# 04_-_Display_Pi_Zero_USB_Host.net
KiCad netlist of a schematic drawn in Altium Designer
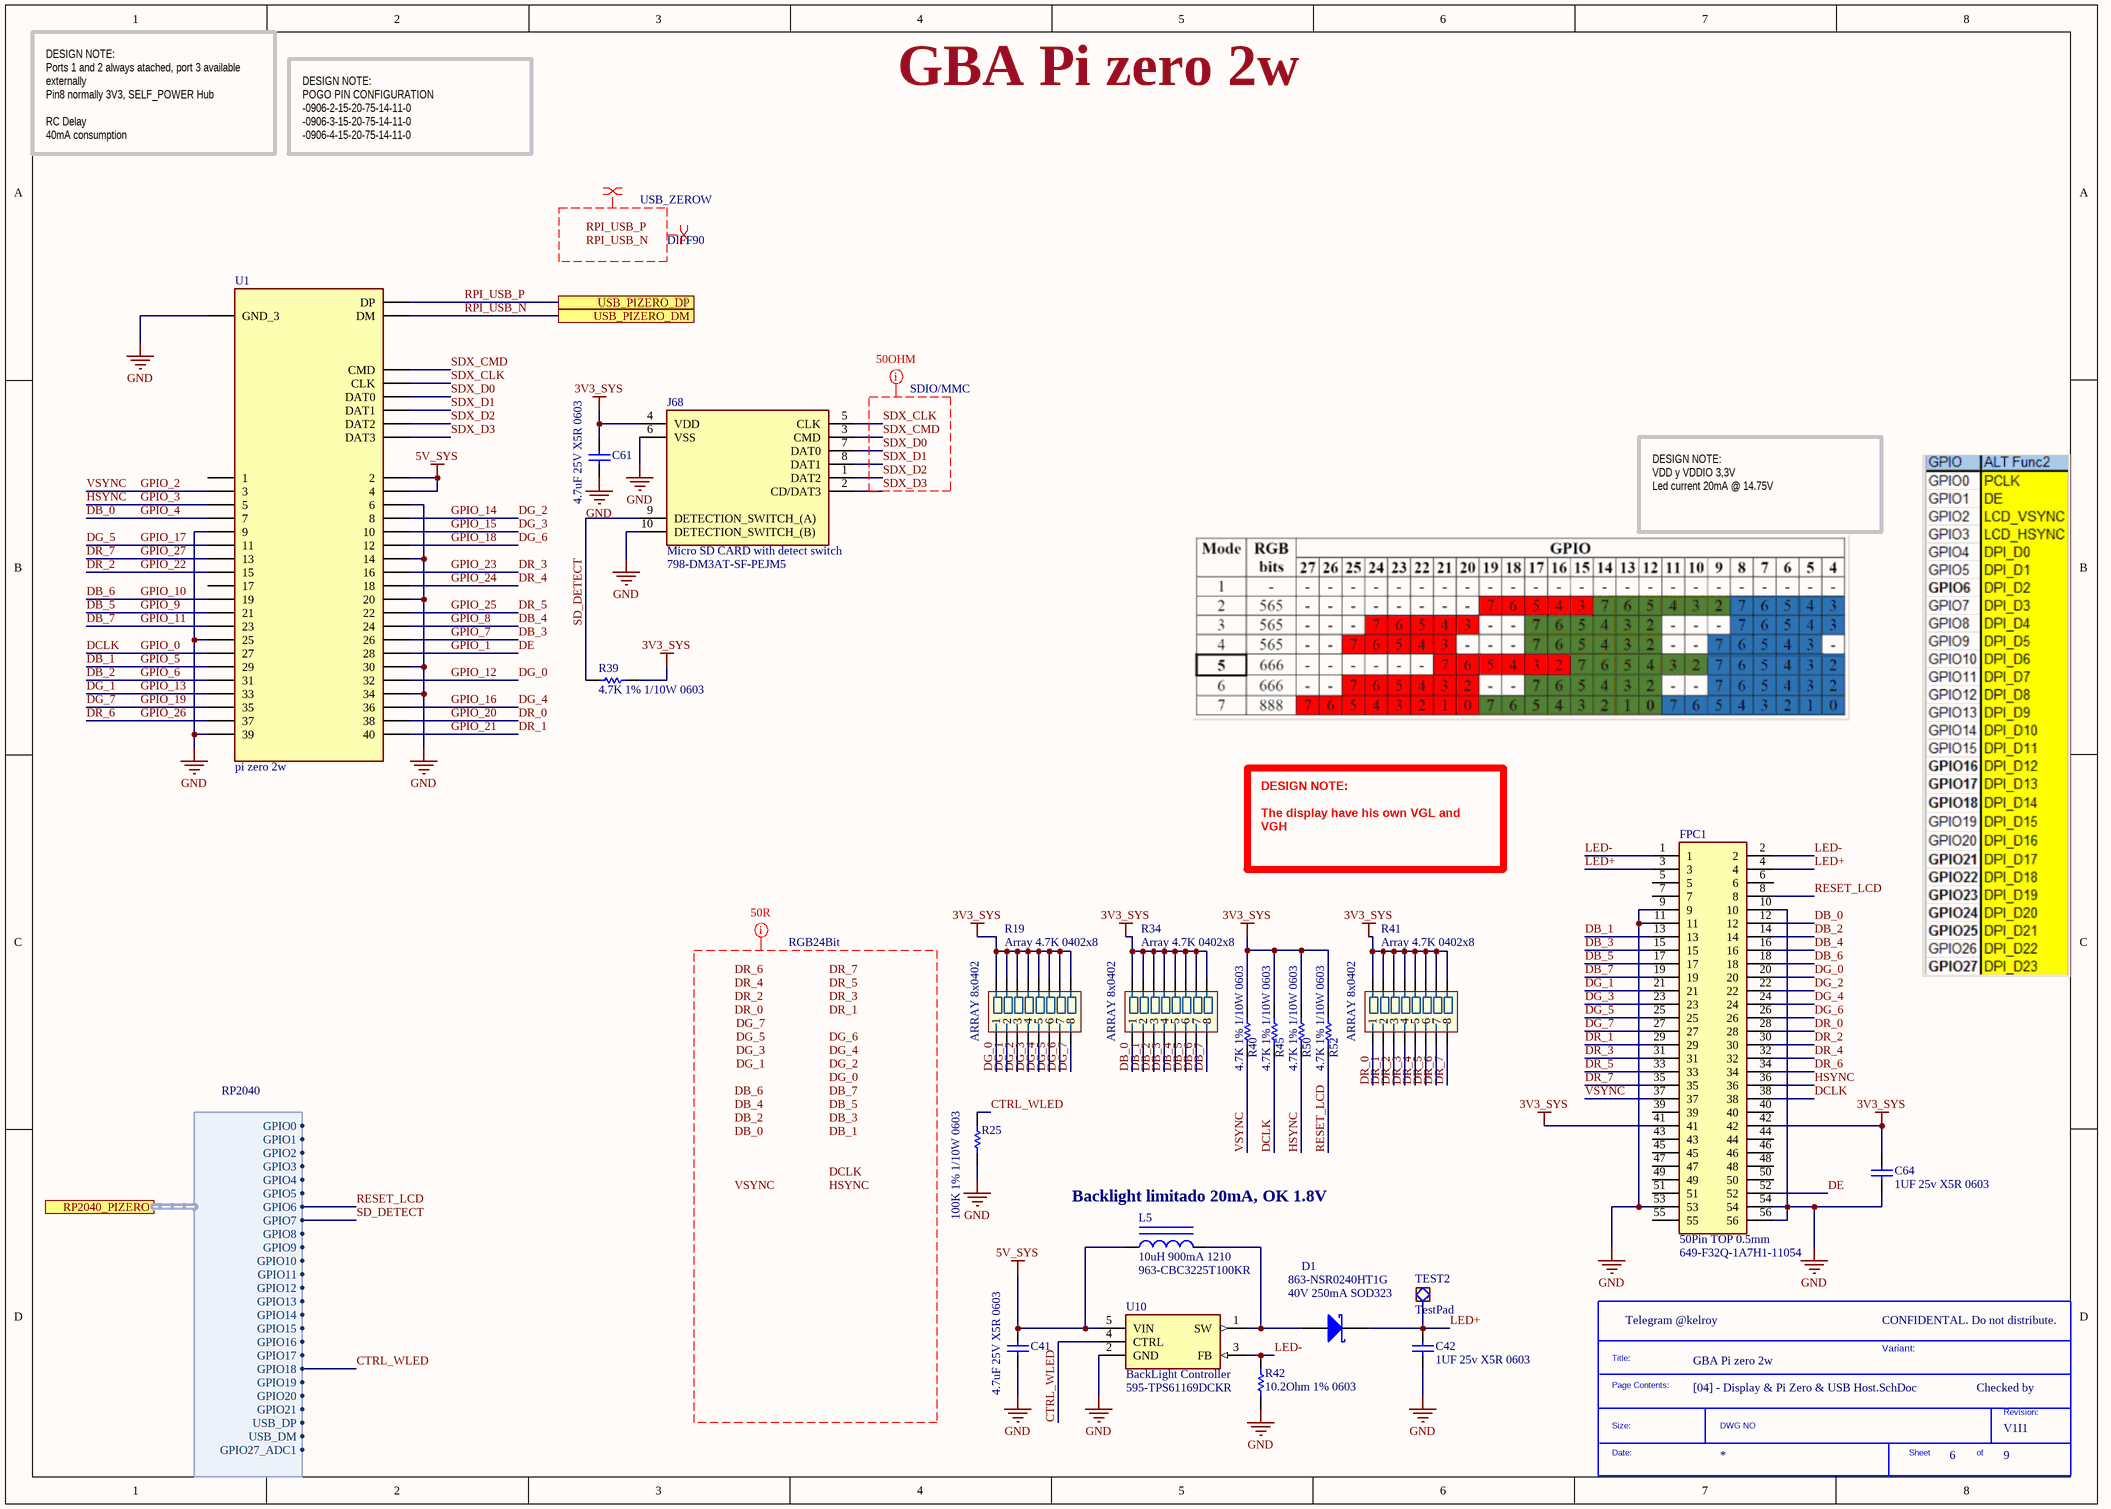
[diagram p0: [04] - Display & Pi Zero & USB Host.SchDoc]

(export (version "E")
  (design (tool "Eeschema 10.0.6"))
  (components
    (comp (ref "C41")
      (value "4.7uF 25V X5R 0603")
      (footprint "C 0603/1608")
      (description "Condensadores de cerámica multicapa (MLCC- SMD/SMT) 0603 25VDC 4.7uF 20% X5R")
      (libsource (lib "Kelboy") (part "TMK107BBJ475MA-T"))
    )
    (comp (ref "C42")
      (value "1UF 25v X5R 0603")
      (footprint "C 0603/1608")
      (description "CAP CER 1UF 25V X5R 0603")
      (fields
        (field (name "MANUFACTURER") "Yageo")
        (field (name "MANUFACTURER PART NUMBER") "CC0603KRX5R8BB105")
      )
      (libsource (lib "CM3Board_V1I2") (part "CC0603KRX5R8BB105"))
    )
    (comp (ref "C61")
      (value "4.7uF 25V X5R 0603")
      (footprint "C 0603/1608")
      (description "Condensadores de cerámica multicapa (MLCC- SMD/SMT) 0603 25VDC 4.7uF 20% X5R")
      (libsource (lib "Kelboy") (part "TMK107BBJ475MA-T"))
    )
    (comp (ref "C64")
      (value "1UF 25v X5R 0603")
      (footprint "C 0603/1608")
      (description "CAP CER 1UF 25V X5R 0603")
      (fields
        (field (name "MANUFACTURER") "Yageo")
        (field (name "MANUFACTURER PART NUMBER") "CC0603KRX5R8BB105")
      )
      (libsource (lib "CM3Board_V1I2") (part "CC0603KRX5R8BB105"))
    )
    (comp (ref "D1")
      (value "40V 250mA SOD323")
      (footprint "SOD-323")
      (description "DIODE SCHOTTKY 40V 250MA SOD323")
      (fields
        (field (name "MANUFACTURER") "ON Semiconductor")
        (field (name "MANUFACTURER PART NUMBER") "NSR0240HT1G")
        (field (name "SUPPLIER PART NUMBER 1") "863-NSR0240HT1G")
      )
      (libsource (lib "DPI_LVDS") (part "NSR0240HT1G"))
    )
    (comp (ref "FPC1")
      (value "50Pin TOP 0.5mm")
      (footprint "XF2M54151AH")
      (description "FPC/FFC Connector Socket 54 Position 0.5mm Top Contact Solder Right Angle Surface Mount T/R")
      (fields
        (field (name "MANUFACTURER") "Amphenol ICC / FCI")
        (field (name "MANUFACTURER PART NUMBER") "F32Q-1A7H1-11054")
        (field (name "SUPPLIER PART NUMBER 1") "649-F32Q-1A7H1-11054")
      )
      (libsource (lib "GBA") (part "F32Q-1A7H1-11054"))
    )
    (comp (ref "J68")
      (value "Micro SD CARD with detect switch")
      (footprint "DM3AT-SF-PEJM5_1")
      (description "CONN MICRO SD CARD PUSH-PUSH R/A")
      (fields (field (name "SUPPLIER PART NUMBER 1") "798-DM3AT-SF-PEJM5"))
      (libsource (lib "Kelboy") (part "DM3AT-SF-PEJM5"))
    )
    (comp (ref "L5")
      (value "10uH 900mA 1210")
      (footprint "L 1210/3225")
      (description "Fixed Inductors 1210 10uH 172.9mOhms +/-10% 900mA HiCur")
      (fields
        (field (name "MANUFACTURER") "Taiyo Yuden")
        (field (name "MANUFACTURER PART NUMBER") "CBC3225T100KR")
        (field (name "SUPPLIER PART NUMBER 1") "963-CBC3225T100KR")
      )
      (libsource (lib "DPI_LVDS") (part "CBC3225T100KR"))
    )
    (comp (ref "R19")
      (value "Array 4.7K 0402x8")
      (footprint "YAG_YC248-M")
      (description "RES ARRAY 8 RES 4.7K OHM 1606")
      (fields (field (name "TOLERANCE") "5%"))
      (libsource (lib "CM3Board_V1I2") (part "YC248-JR-074K7L"))
    )
    (comp (ref "R25")
      (value "100K 1% 1/10W 0603")
      (footprint "R 0603/1608")
      (description "RES SMD 100K OHM 1% 1/10W 0603")
      (fields
        (field (name "MANUFACTURER") "Yageo")
        (field (name "MANUFACTURER PART NUMBER") "RC0603FR-07100KL")
      )
      (libsource (lib "altium-import") (part "root_1_RC0603FR-07100KL_"))
    )
    (comp (ref "R34")
      (value "Array 4.7K 0402x8")
      (footprint "YAG_YC248-M")
      (description "RES ARRAY 8 RES 4.7K OHM 1606")
      (fields (field (name "TOLERANCE") "5%"))
      (libsource (lib "CM3Board_V1I2") (part "YC248-JR-074K7L"))
    )
    (comp (ref "R39")
      (value "4.7K 1% 1/10W 0603")
      (footprint "R 0603/1608")
      (description "RES SMD 4.7K OHM 1% 1/10W 0603")
      (fields
        (field (name "MANUFACTURER") "Yageo")
        (field (name "MANUFACTURER PART NUMBER") "RC0603FR-074K7L")
      )
      (libsource (lib "CM3Board_V1I2") (part "RC0603FR-074K7L"))
    )
    (comp (ref "R40")
      (value "4.7K 1% 1/10W 0603")
      (footprint "R 0603/1608")
      (description "RES SMD 4.7K OHM 1% 1/10W 0603")
      (fields
        (field (name "MANUFACTURER") "Yageo")
        (field (name "MANUFACTURER PART NUMBER") "RC0603FR-074K7L")
      )
      (libsource (lib "CM3Board_V1I2") (part "RC0603FR-074K7L"))
    )
    (comp (ref "R41")
      (value "Array 4.7K 0402x8")
      (footprint "YAG_YC248-M")
      (description "RES ARRAY 8 RES 4.7K OHM 1606")
      (fields (field (name "TOLERANCE") "5%"))
      (libsource (lib "CM3Board_V1I2") (part "YC248-JR-074K7L"))
    )
    (comp (ref "R42")
      (value "10.2Ohm 1% 0603")
      (footprint "R 0603/1608")
      (description "RES SMD 10.2 OHM 1% 1/10W 0603")
      (fields (field (name "TOLERANCE") "1%"))
      (libsource (lib "Kelboy") (part "RC0603FR-0710R2L"))
    )
    (comp (ref "R45")
      (value "4.7K 1% 1/10W 0603")
      (footprint "R 0603/1608")
      (description "RES SMD 4.7K OHM 1% 1/10W 0603")
      (fields
        (field (name "MANUFACTURER") "Yageo")
        (field (name "MANUFACTURER PART NUMBER") "RC0603FR-074K7L")
      )
      (libsource (lib "CM3Board_V1I2") (part "RC0603FR-074K7L"))
    )
    (comp (ref "R50")
      (value "4.7K 1% 1/10W 0603")
      (footprint "R 0603/1608")
      (description "RES SMD 4.7K OHM 1% 1/10W 0603")
      (fields
        (field (name "MANUFACTURER") "Yageo")
        (field (name "MANUFACTURER PART NUMBER") "RC0603FR-074K7L")
      )
      (libsource (lib "CM3Board_V1I2") (part "RC0603FR-074K7L"))
    )
    (comp (ref "R52")
      (value "4.7K 1% 1/10W 0603")
      (footprint "R 0603/1608")
      (description "RES SMD 4.7K OHM 1% 1/10W 0603")
      (fields
        (field (name "MANUFACTURER") "Yageo")
        (field (name "MANUFACTURER PART NUMBER") "RC0603FR-074K7L")
      )
      (libsource (lib "CM3Board_V1I2") (part "RC0603FR-074K7L"))
    )
    (comp (ref "TEST2")
      (value "TestPad")
      (footprint "TestPad")
      (description "Probe Pad, SMT, ROUND, 2.0MM")
      (libsource (lib "CM3Board") (part "PP_SMT_ROUND_2MM"))
    )
    (comp (ref "U1")
      (value "pi zero 2w")
      (footprint "Pi 2 Zero W - Release")
      (description "Comprar los pogo 575-906015  x 60 y los de los tornillos x4 710-9774025151R")
      (libsource (lib "GBA") (part "PI ZERO 2W"))
    )
    (comp (ref "U10")
      (value "BackLight Controller")
      (footprint "SOT65P210X110-5N")
      (description "IC LED DRVR RGLTR DIM 1.8A SC70")
      (fields
        (field (name "MANUFACTURER") "Texas Instruments")
        (field (name "MANUFACTURER PART NUMBER") "TPS61169DCKR")
        (field (name "SUPPLIER PART NUMBER 1") "595-TPS61169DCKR")
      )
      (libsource (lib "DPI_LVDS") (part "TPS61169DCKR"))
    )
  )
  (nets
    (net (code "2") (name "/CTRL_WLED") (class "Default")
      (node (ref "R25") (pin "2") (pinfunction "2_2") (pintype "passive"))
      (node (ref "U10") (pin "4") (pinfunction "CTRL_4") (pintype "passive"))
    )
    (net (code "3") (name "/DB_0") (class "Default")
      (node (ref "FPC1") (pin "12") (pinfunction "12_12") (pintype "passive"))
      (node (ref "R34") (pin "1") (pinfunction "1_1") (pintype "passive"))
      (node (ref "U1") (pin "7") (pinfunction "7_7") (pintype "passive"))
    )
    (net (code "4") (name "/DB_1") (class "Default")
      (node (ref "FPC1") (pin "13") (pinfunction "13_13") (pintype "passive"))
      (node (ref "R34") (pin "2") (pinfunction "2_2") (pintype "passive"))
      (node (ref "U1") (pin "29") (pinfunction "29_29") (pintype "passive"))
    )
    (net (code "5") (name "/DB_2") (class "Default")
      (node (ref "FPC1") (pin "14") (pinfunction "14_14") (pintype "passive"))
      (node (ref "R34") (pin "3") (pinfunction "3_3") (pintype "passive"))
      (node (ref "U1") (pin "31") (pinfunction "31_31") (pintype "passive"))
    )
    (net (code "6") (name "/DB_3") (class "Default")
      (node (ref "FPC1") (pin "15") (pinfunction "15_15") (pintype "passive"))
      (node (ref "R34") (pin "4") (pinfunction "4_4") (pintype "passive"))
      (node (ref "U1") (pin "26") (pinfunction "26_26") (pintype "passive"))
    )
    (net (code "7") (name "/DB_4") (class "Default")
      (node (ref "FPC1") (pin "16") (pinfunction "16_16") (pintype "passive"))
      (node (ref "R34") (pin "5") (pinfunction "5_5") (pintype "passive"))
      (node (ref "U1") (pin "24") (pinfunction "24_24") (pintype "passive"))
    )
    (net (code "8") (name "/DB_5") (class "Default")
      (node (ref "FPC1") (pin "17") (pinfunction "17_17") (pintype "passive"))
      (node (ref "R34") (pin "6") (pinfunction "6_6") (pintype "passive"))
      (node (ref "U1") (pin "21") (pinfunction "21_21") (pintype "passive"))
    )
    (net (code "9") (name "/DB_6") (class "Default")
      (node (ref "FPC1") (pin "18") (pinfunction "18_18") (pintype "passive"))
      (node (ref "R34") (pin "7") (pinfunction "7_7") (pintype "passive"))
      (node (ref "U1") (pin "19") (pinfunction "19_19") (pintype "passive"))
    )
    (net (code "10") (name "/DB_7") (class "Default")
      (node (ref "FPC1") (pin "19") (pinfunction "19_19") (pintype "passive"))
      (node (ref "R34") (pin "8") (pinfunction "8_8") (pintype "passive"))
      (node (ref "U1") (pin "23") (pinfunction "23_23") (pintype "passive"))
    )
    (net (code "11") (name "/DCLK") (class "Default")
      (node (ref "FPC1") (pin "38") (pinfunction "38_38") (pintype "passive"))
      (node (ref "R45") (pin "1") (pinfunction "1_1") (pintype "passive"))
      (node (ref "U1") (pin "27") (pinfunction "27_27") (pintype "passive"))
    )
    (net (code "12") (name "/DE") (class "Default")
      (node (ref "FPC1") (pin "52") (pinfunction "52_52") (pintype "passive"))
      (node (ref "U1") (pin "28") (pinfunction "28_28") (pintype "passive"))
    )
    (net (code "13") (name "/DG_0") (class "Default")
      (node (ref "FPC1") (pin "20") (pinfunction "20_20") (pintype "passive"))
      (node (ref "R19") (pin "1") (pinfunction "1_1") (pintype "passive"))
      (node (ref "U1") (pin "32") (pinfunction "32_32") (pintype "passive"))
    )
    (net (code "14") (name "/DG_1") (class "Default")
      (node (ref "FPC1") (pin "21") (pinfunction "21_21") (pintype "passive"))
      (node (ref "R19") (pin "2") (pinfunction "2_2") (pintype "passive"))
      (node (ref "U1") (pin "33") (pinfunction "33_33") (pintype "passive"))
    )
    (net (code "15") (name "/DG_2") (class "Default")
      (node (ref "FPC1") (pin "22") (pinfunction "22_22") (pintype "passive"))
      (node (ref "R19") (pin "3") (pinfunction "3_3") (pintype "passive"))
      (node (ref "U1") (pin "8") (pinfunction "8_8") (pintype "passive"))
    )
    (net (code "16") (name "/DG_3") (class "Default")
      (node (ref "FPC1") (pin "23") (pinfunction "23_23") (pintype "passive"))
      (node (ref "R19") (pin "4") (pinfunction "4_4") (pintype "passive"))
      (node (ref "U1") (pin "10") (pinfunction "10_10") (pintype "passive"))
    )
    (net (code "17") (name "/DG_4") (class "Default")
      (node (ref "FPC1") (pin "24") (pinfunction "24_24") (pintype "passive"))
      (node (ref "R19") (pin "5") (pinfunction "5_5") (pintype "passive"))
      (node (ref "U1") (pin "36") (pinfunction "36_36") (pintype "passive"))
    )
    (net (code "18") (name "/DG_5") (class "Default")
      (node (ref "FPC1") (pin "25") (pinfunction "25_25") (pintype "passive"))
      (node (ref "R19") (pin "6") (pinfunction "6_6") (pintype "passive"))
      (node (ref "U1") (pin "11") (pinfunction "11_11") (pintype "passive"))
    )
    (net (code "19") (name "/DG_6") (class "Default")
      (node (ref "FPC1") (pin "26") (pinfunction "26_26") (pintype "passive"))
      (node (ref "R19") (pin "7") (pinfunction "7_7") (pintype "passive"))
      (node (ref "U1") (pin "12") (pinfunction "12_12") (pintype "passive"))
    )
    (net (code "20") (name "/DG_7") (class "Default")
      (node (ref "FPC1") (pin "27") (pinfunction "27_27") (pintype "passive"))
      (node (ref "R19") (pin "8") (pinfunction "8_8") (pintype "passive"))
      (node (ref "U1") (pin "35") (pinfunction "35_35") (pintype "passive"))
    )
    (net (code "21") (name "/DR_0") (class "Default")
      (node (ref "FPC1") (pin "28") (pinfunction "28_28") (pintype "passive"))
      (node (ref "R41") (pin "1") (pinfunction "1_1") (pintype "passive"))
      (node (ref "U1") (pin "38") (pinfunction "38_38") (pintype "passive"))
    )
    (net (code "22") (name "/DR_1") (class "Default")
      (node (ref "FPC1") (pin "29") (pinfunction "29_29") (pintype "passive"))
      (node (ref "R41") (pin "2") (pinfunction "2_2") (pintype "passive"))
      (node (ref "U1") (pin "40") (pinfunction "40_40") (pintype "passive"))
    )
    (net (code "23") (name "/DR_2") (class "Default")
      (node (ref "FPC1") (pin "30") (pinfunction "30_30") (pintype "passive"))
      (node (ref "R41") (pin "3") (pinfunction "3_3") (pintype "passive"))
      (node (ref "U1") (pin "15") (pinfunction "15_15") (pintype "passive"))
    )
    (net (code "24") (name "/DR_3") (class "Default")
      (node (ref "FPC1") (pin "31") (pinfunction "31_31") (pintype "passive"))
      (node (ref "R41") (pin "4") (pinfunction "4_4") (pintype "passive"))
      (node (ref "U1") (pin "16") (pinfunction "16_16") (pintype "passive"))
    )
    (net (code "25") (name "/DR_4") (class "Default")
      (node (ref "FPC1") (pin "32") (pinfunction "32_32") (pintype "passive"))
      (node (ref "R41") (pin "5") (pinfunction "5_5") (pintype "passive"))
      (node (ref "U1") (pin "18") (pinfunction "18_18") (pintype "passive"))
    )
    (net (code "26") (name "/DR_5") (class "Default")
      (node (ref "FPC1") (pin "33") (pinfunction "33_33") (pintype "passive"))
      (node (ref "R41") (pin "6") (pinfunction "6_6") (pintype "passive"))
      (node (ref "U1") (pin "22") (pinfunction "22_22") (pintype "passive"))
    )
    (net (code "27") (name "/DR_6") (class "Default")
      (node (ref "FPC1") (pin "34") (pinfunction "34_34") (pintype "passive"))
      (node (ref "R41") (pin "7") (pinfunction "7_7") (pintype "passive"))
      (node (ref "U1") (pin "37") (pinfunction "37_37") (pintype "passive"))
    )
    (net (code "28") (name "/DR_7") (class "Default")
      (node (ref "FPC1") (pin "35") (pinfunction "35_35") (pintype "passive"))
      (node (ref "R41") (pin "8") (pinfunction "8_8") (pintype "passive"))
      (node (ref "U1") (pin "13") (pinfunction "13_13") (pintype "passive"))
    )
    (net (code "29") (name "/GPIO_2") (class "Default")
      (node (ref "FPC1") (pin "37") (pinfunction "37_37") (pintype "passive"))
      (node (ref "R40") (pin "1") (pinfunction "1_1") (pintype "passive"))
      (node (ref "U1") (pin "3") (pinfunction "3_3") (pintype "passive"))
    )
    (net (code "30") (name "/GPIO_3") (class "Default")
      (node (ref "FPC1") (pin "36") (pinfunction "36_36") (pintype "passive"))
      (node (ref "R50") (pin "1") (pinfunction "1_1") (pintype "passive"))
      (node (ref "U1") (pin "5") (pinfunction "5_5") (pintype "passive"))
    )
    (net (code "31") (name "/LED+") (class "Default")
      (node (ref "C42") (pin "1") (pinfunction "1_1") (pintype "passive"))
      (node (ref "D1") (pin "1") (pinfunction "K_1") (pintype "passive"))
      (node (ref "FPC1") (pin "3") (pinfunction "3_3") (pintype "passive"))
      (node (ref "FPC1") (pin "4") (pinfunction "4_4") (pintype "passive"))
      (node (ref "TEST2") (pin "1") (pinfunction "1_1") (pintype "passive"))
    )
    (net (code "32") (name "/LED-") (class "Default")
      (node (ref "FPC1") (pin "1") (pinfunction "1_1") (pintype "passive"))
      (node (ref "FPC1") (pin "2") (pinfunction "2_2") (pintype "passive"))
      (node (ref "R42") (pin "2") (pinfunction "2_2") (pintype "passive"))
      (node (ref "U10") (pin "3") (pinfunction "FB_3") (pintype "input"))
    )
    (net (code "33") (name "/RESET_LCD") (class "Default")
      (node (ref "FPC1") (pin "8") (pinfunction "8_8") (pintype "passive"))
      (node (ref "R52") (pin "1") (pinfunction "1_1") (pintype "passive"))
    )
    (net (code "34") (name "/RPI_USB_N") (class "Default")
      (node (ref "U1") (pin "DM") (pinfunction "DM_DM") (pintype "passive"))
    )
    (net (code "35") (name "/RPI_USB_P") (class "Default")
      (node (ref "U1") (pin "DP") (pinfunction "DP_DP") (pintype "passive"))
    )
    (net (code "36") (name "/SDX_CLK") (class "Default")
      (node (ref "J68") (pin "5") (pinfunction "CLK_5") (pintype "passive"))
      (node (ref "U1") (pin "CLK") (pinfunction "CLK_CLK") (pintype "passive"))
    )
    (net (code "37") (name "/SDX_CMD") (class "Default")
      (node (ref "J68") (pin "3") (pinfunction "CMD_3") (pintype "passive"))
      (node (ref "U1") (pin "CMD") (pinfunction "CMD_CMD") (pintype "passive"))
    )
    (net (code "38") (name "/SDX_D0") (class "Default")
      (node (ref "J68") (pin "7") (pinfunction "DAT0_7") (pintype "passive"))
      (node (ref "U1") (pin "DAT0") (pinfunction "DAT0_DAT0") (pintype "passive"))
    )
    (net (code "39") (name "/SDX_D1") (class "Default")
      (node (ref "J68") (pin "8") (pinfunction "DAT1_8") (pintype "passive"))
      (node (ref "U1") (pin "DAT1") (pinfunction "DAT1_DAT1") (pintype "passive"))
    )
    (net (code "40") (name "/SDX_D2") (class "Default")
      (node (ref "J68") (pin "1") (pinfunction "DAT2_1") (pintype "passive"))
      (node (ref "U1") (pin "DAT2") (pinfunction "DAT2_DAT2") (pintype "passive"))
    )
    (net (code "41") (name "/SDX_D3") (class "Default")
      (node (ref "J68") (pin "2") (pinfunction "CD/DAT3_2") (pintype "passive"))
      (node (ref "U1") (pin "DAT3") (pinfunction "DAT3_DAT3") (pintype "passive"))
    )
    (net (code "42") (name "/SD_DETECT") (class "Default")
      (node (ref "J68") (pin "9") (pinfunction "DETECTION_SWITCH_(A)_9") (pintype "passive"))
      (node (ref "R39") (pin "2") (pinfunction "2_2") (pintype "passive"))
    )
    (net (code "44") (name "3V3_SYS") (class "Default")
      (node (ref "C61") (pin "1") (pinfunction "1_1") (pintype "passive"))
      (node (ref "C64") (pin "1") (pinfunction "1_1") (pintype "passive"))
      (node (ref "FPC1") (pin "41") (pinfunction "41_41") (pintype "passive"))
      (node (ref "FPC1") (pin "42") (pinfunction "42_42") (pintype "passive"))
      (node (ref "J68") (pin "4") (pinfunction "VDD_4") (pintype "passive"))
      (node (ref "R19") (pin "10") (pinfunction "10_10") (pintype "passive"))
      (node (ref "R19") (pin "11") (pinfunction "11_11") (pintype "passive"))
      (node (ref "R19") (pin "12") (pinfunction "12_12") (pintype "passive"))
      (node (ref "R19") (pin "13") (pinfunction "13_13") (pintype "passive"))
      (node (ref "R19") (pin "14") (pinfunction "14_14") (pintype "passive"))
      (node (ref "R19") (pin "15") (pinfunction "15_15") (pintype "passive"))
      (node (ref "R19") (pin "16") (pinfunction "16_16") (pintype "passive"))
      (node (ref "R19") (pin "9") (pinfunction "9_9") (pintype "passive"))
      (node (ref "R34") (pin "10") (pinfunction "10_10") (pintype "passive"))
      (node (ref "R34") (pin "11") (pinfunction "11_11") (pintype "passive"))
      (node (ref "R34") (pin "12") (pinfunction "12_12") (pintype "passive"))
      (node (ref "R34") (pin "13") (pinfunction "13_13") (pintype "passive"))
      (node (ref "R34") (pin "14") (pinfunction "14_14") (pintype "passive"))
      (node (ref "R34") (pin "15") (pinfunction "15_15") (pintype "passive"))
      (node (ref "R34") (pin "16") (pinfunction "16_16") (pintype "passive"))
      (node (ref "R34") (pin "9") (pinfunction "9_9") (pintype "passive"))
      (node (ref "R39") (pin "1") (pinfunction "1_1") (pintype "passive"))
      (node (ref "R40") (pin "2") (pinfunction "2_2") (pintype "passive"))
      (node (ref "R41") (pin "10") (pinfunction "10_10") (pintype "passive"))
      (node (ref "R41") (pin "11") (pinfunction "11_11") (pintype "passive"))
      (node (ref "R41") (pin "12") (pinfunction "12_12") (pintype "passive"))
      (node (ref "R41") (pin "13") (pinfunction "13_13") (pintype "passive"))
      (node (ref "R41") (pin "14") (pinfunction "14_14") (pintype "passive"))
      (node (ref "R41") (pin "15") (pinfunction "15_15") (pintype "passive"))
      (node (ref "R41") (pin "16") (pinfunction "16_16") (pintype "passive"))
      (node (ref "R41") (pin "9") (pinfunction "9_9") (pintype "passive"))
      (node (ref "R45") (pin "2") (pinfunction "2_2") (pintype "passive"))
      (node (ref "R50") (pin "2") (pinfunction "2_2") (pintype "passive"))
      (node (ref "R52") (pin "2") (pinfunction "2_2") (pintype "passive"))
    )
    (net (code "45") (name "5V_SYS") (class "Default")
      (node (ref "C41") (pin "1") (pinfunction "1_1") (pintype "passive"))
      (node (ref "L5") (pin "1") (pinfunction "1_1") (pintype "passive"))
      (node (ref "U1") (pin "2") (pinfunction "2_2") (pintype "passive"))
      (node (ref "U1") (pin "4") (pinfunction "4_4") (pintype "passive"))
      (node (ref "U10") (pin "5") (pinfunction "VIN_5") (pintype "power_in"))
    )
    (net (code "46") (name "GND") (class "Default")
      (node (ref "C41") (pin "2") (pinfunction "2_2") (pintype "passive"))
      (node (ref "C42") (pin "2") (pinfunction "2_2") (pintype "passive"))
      (node (ref "C61") (pin "2") (pinfunction "2_2") (pintype "passive"))
      (node (ref "C64") (pin "2") (pinfunction "2_2") (pintype "passive"))
      (node (ref "FPC1") (pin "10") (pinfunction "10_10") (pintype "passive"))
      (node (ref "FPC1") (pin "11") (pinfunction "11_11") (pintype "passive"))
      (node (ref "FPC1") (pin "53") (pinfunction "53_53") (pintype "passive"))
      (node (ref "FPC1") (pin "54") (pinfunction "54_54") (pintype "passive"))
      (node (ref "FPC1") (pin "56") (pinfunction "56_56") (pintype "passive"))
      (node (ref "FPC1") (pin "9") (pinfunction "9_9") (pintype "passive"))
      (node (ref "J68") (pin "10") (pinfunction "DETECTION_SWITCH_(B)_10") (pintype "passive"))
      (node (ref "J68") (pin "6") (pinfunction "VSS_6") (pintype "passive"))
      (node (ref "R25") (pin "1") (pinfunction "1_1") (pintype "passive"))
      (node (ref "R42") (pin "1") (pinfunction "1_1") (pintype "passive"))
      (node (ref "U1") (pin "14") (pinfunction "14_14") (pintype "passive"))
      (node (ref "U1") (pin "20") (pinfunction "20_20") (pintype "passive"))
      (node (ref "U1") (pin "25") (pinfunction "25_25") (pintype "passive"))
      (node (ref "U1") (pin "30") (pinfunction "30_30") (pintype "passive"))
      (node (ref "U1") (pin "34") (pinfunction "34_34") (pintype "passive"))
      (node (ref "U1") (pin "39") (pinfunction "39_39") (pintype "passive"))
      (node (ref "U1") (pin "6") (pinfunction "6_6") (pintype "passive"))
      (node (ref "U1") (pin "9") (pinfunction "9_9") (pintype "passive"))
      (node (ref "U1") (pin "GND_3") (pinfunction "GND_3_GND_3") (pintype "passive"))
      (node (ref "U10") (pin "2") (pinfunction "GND_2") (pintype "power_in"))
    )
    (net (code "47") (name "Net-(D1-A)") (class "Default")
      (node (ref "D1") (pin "2") (pinfunction "A_2") (pintype "passive"))
      (node (ref "L5") (pin "2") (pinfunction "2_2") (pintype "passive"))
      (node (ref "U10") (pin "1") (pinfunction "SW_1") (pintype "output"))
    )
    (net (code "48") (name "unconnected-(FPC1-Pad5)") (class "Default")
      (node (ref "FPC1") (pin "5") (pinfunction "5_5") (pintype "passive"))
    )
    (net (code "49") (name "unconnected-(FPC1-Pad6)") (class "Default")
      (node (ref "FPC1") (pin "6") (pinfunction "6_6") (pintype "passive"))
    )
    (net (code "50") (name "unconnected-(FPC1-Pad7)") (class "Default")
      (node (ref "FPC1") (pin "7") (pinfunction "7_7") (pintype "passive"))
    )
    (net (code "51") (name "unconnected-(FPC1-Pad39)") (class "Default")
      (node (ref "FPC1") (pin "39") (pinfunction "39_39") (pintype "passive"))
    )
    (net (code "52") (name "unconnected-(FPC1-Pad40)") (class "Default")
      (node (ref "FPC1") (pin "40") (pinfunction "40_40") (pintype "passive"))
    )
    (net (code "53") (name "unconnected-(FPC1-Pad43)") (class "Default")
      (node (ref "FPC1") (pin "43") (pinfunction "43_43") (pintype "passive"))
    )
    (net (code "54") (name "unconnected-(FPC1-Pad44)") (class "Default")
      (node (ref "FPC1") (pin "44") (pinfunction "44_44") (pintype "passive"))
    )
    (net (code "55") (name "unconnected-(FPC1-Pad45)") (class "Default")
      (node (ref "FPC1") (pin "45") (pinfunction "45_45") (pintype "passive"))
    )
    (net (code "56") (name "unconnected-(FPC1-Pad46)") (class "Default")
      (node (ref "FPC1") (pin "46") (pinfunction "46_46") (pintype "passive"))
    )
    (net (code "57") (name "unconnected-(FPC1-Pad47)") (class "Default")
      (node (ref "FPC1") (pin "47") (pinfunction "47_47") (pintype "passive"))
    )
    (net (code "58") (name "unconnected-(FPC1-Pad48)") (class "Default")
      (node (ref "FPC1") (pin "48") (pinfunction "48_48") (pintype "passive"))
    )
    (net (code "59") (name "unconnected-(FPC1-Pad49)") (class "Default")
      (node (ref "FPC1") (pin "49") (pinfunction "49_49") (pintype "passive"))
    )
    (net (code "60") (name "unconnected-(FPC1-Pad50)") (class "Default")
      (node (ref "FPC1") (pin "50") (pinfunction "50_50") (pintype "passive"))
    )
    (net (code "61") (name "unconnected-(FPC1-Pad51)") (class "Default")
      (node (ref "FPC1") (pin "51") (pinfunction "51_51") (pintype "passive"))
    )
    (net (code "62") (name "unconnected-(FPC1-Pad55)") (class "Default")
      (node (ref "FPC1") (pin "55") (pinfunction "55_55") (pintype "passive"))
    )
    (net (code "63") (name "unconnected-(U1-Pad1)") (class "Default")
      (node (ref "U1") (pin "1") (pinfunction "1_1") (pintype "passive"))
    )
    (net (code "64") (name "unconnected-(U1-Pad17)") (class "Default")
      (node (ref "U1") (pin "17") (pinfunction "17_17") (pintype "passive"))
    )
  )
)
